# Rib-BabyBack.net
KiCad netlist of a schematic drawn in EAGLE
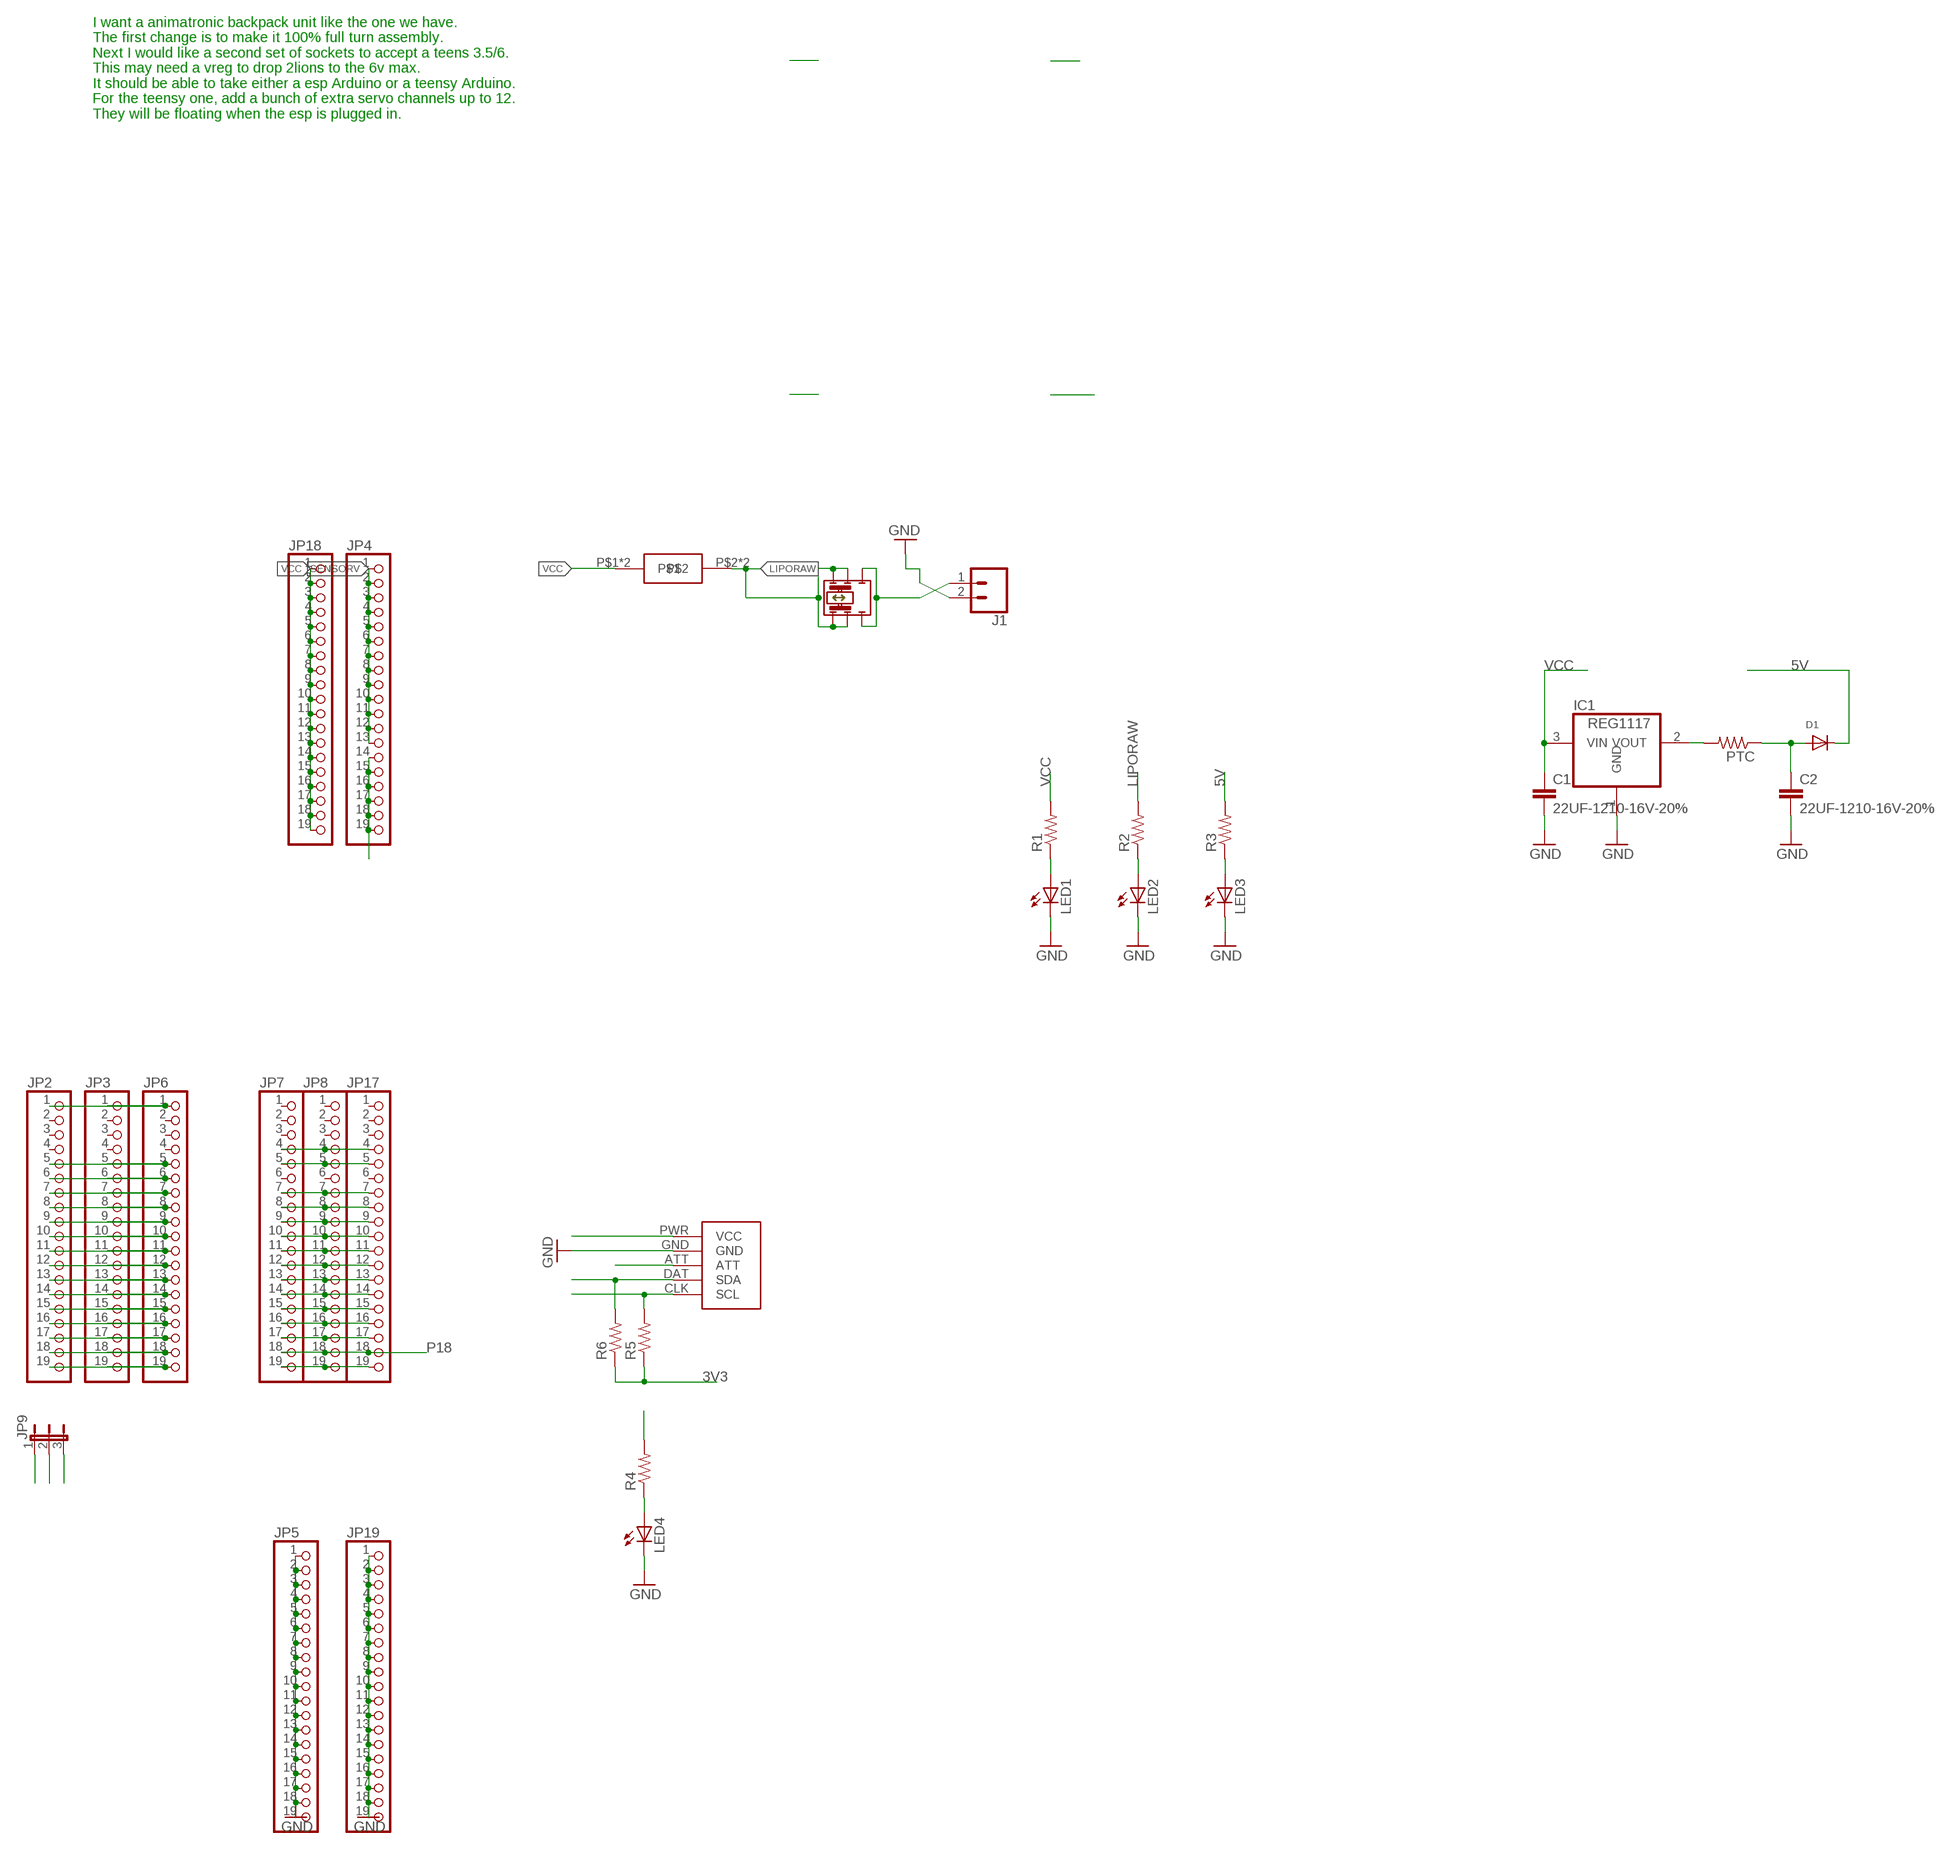
[diagram p0: schematic, sheet 1]

(export (version "E")
  (design (tool "Eeschema 10.0.6"))
  (components
    (comp (ref "C1")
      (value "22UF-1210-16V-20%")
      (footprint "eagle-import:1210")
      (libsource (lib "eagle-import") (part "22UF-1210-16V-20%"))
    )
    (comp (ref "C2")
      (value "22UF-1210-16V-20%")
      (footprint "eagle-import:1210")
      (libsource (lib "eagle-import") (part "22UF-1210-16V-20%"))
    )
    (comp (ref "D1")
      (value "DIODESOD-523")
      (footprint "eagle-import:SOD-523")
      (libsource (lib "eagle-import") (part "DIODESOD-523"))
    )
    (comp (ref "F4")
      (value "3557-2")
      (footprint "eagle-import:3557-2")
      (libsource (lib "eagle-import") (part "3557-2"))
    )
    (comp (ref "IC1")
      (value "REG1117")
      (footprint "eagle-import:SOT223")
      (libsource (lib "eagle-import") (part "REG1117"))
    )
    (comp (ref "J1")
      (value "CONN_023.5MM_LOCK")
      (footprint "eagle-import:SCREWTERMINAL-3.5MM-2_LOCK")
      (libsource (lib "eagle-import") (part "CONN_023.5MM_LOCK"))
    )
    (comp (ref "JP2")
      (value "PINHD-1X19")
      (footprint "eagle-import:1X19")
      (libsource (lib "eagle-import") (part "PINHD-1X19"))
    )
    (comp (ref "JP3")
      (value "PINHD-1X19")
      (footprint "eagle-import:1X19")
      (libsource (lib "eagle-import") (part "PINHD-1X19"))
    )
    (comp (ref "JP4")
      (value "PINHD-1X19")
      (footprint "eagle-import:1X19")
      (libsource (lib "eagle-import") (part "PINHD-1X19"))
    )
    (comp (ref "JP5")
      (value "PINHD-1X19")
      (footprint "eagle-import:1X19")
      (libsource (lib "eagle-import") (part "PINHD-1X19"))
    )
    (comp (ref "JP6")
      (value "PINHD-1X19")
      (footprint "eagle-import:1X19")
      (libsource (lib "eagle-import") (part "PINHD-1X19"))
    )
    (comp (ref "JP7")
      (value "PINHD-1X19")
      (footprint "eagle-import:1X19")
      (libsource (lib "eagle-import") (part "PINHD-1X19"))
    )
    (comp (ref "JP8")
      (value "PINHD-1X19")
      (footprint "eagle-import:1X19")
      (libsource (lib "eagle-import") (part "PINHD-1X19"))
    )
    (comp (ref "JP9")
      (value "JP2E")
      (footprint "eagle-import:JP2")
      (libsource (lib "eagle-import") (part "JP2E"))
    )
    (comp (ref "JP17")
      (value "PINHD-1X19")
      (footprint "eagle-import:1X19")
      (libsource (lib "eagle-import") (part "PINHD-1X19"))
    )
    (comp (ref "JP18")
      (value "PINHD-1X19")
      (footprint "eagle-import:1X19")
      (libsource (lib "eagle-import") (part "PINHD-1X19"))
    )
    (comp (ref "JP19")
      (value "PINHD-1X19")
      (footprint "eagle-import:1X19")
      (libsource (lib "eagle-import") (part "PINHD-1X19"))
    )
    (comp (ref "LED1")
      (value "LED_ESML0603")
      (footprint "eagle-import:LED_SML0603")
      (libsource (lib "eagle-import") (part "LED_ESML0603"))
    )
    (comp (ref "LED2")
      (value "LED_ESML0603")
      (footprint "eagle-import:LED_SML0603")
      (libsource (lib "eagle-import") (part "LED_ESML0603"))
    )
    (comp (ref "LED3")
      (value "LED_ESML0603")
      (footprint "eagle-import:LED_SML0603")
      (libsource (lib "eagle-import") (part "LED_ESML0603"))
    )
    (comp (ref "LED4")
      (value "LED_ESML0603")
      (footprint "eagle-import:LED_SML0603")
      (libsource (lib "eagle-import") (part "LED_ESML0603"))
    )
    (comp (ref "PTC")
      (value "R-US_R0805")
      (footprint "eagle-import:R0805")
      (libsource (lib "eagle-import") (part "R-US_R0805"))
    )
    (comp (ref "R1")
      (value "R-US_R0603")
      (footprint "eagle-import:R0603")
      (libsource (lib "eagle-import") (part "R-US_R0603"))
    )
    (comp (ref "R2")
      (value "R-US_R0603")
      (footprint "eagle-import:R0603")
      (libsource (lib "eagle-import") (part "R-US_R0603"))
    )
    (comp (ref "R3")
      (value "R-US_R0603")
      (footprint "eagle-import:R0603")
      (libsource (lib "eagle-import") (part "R-US_R0603"))
    )
    (comp (ref "R4")
      (value "R-US_R0603")
      (footprint "eagle-import:R0603")
      (libsource (lib "eagle-import") (part "R-US_R0603"))
    )
    (comp (ref "R5")
      (value "R-US_R0603")
      (footprint "eagle-import:R0603")
      (libsource (lib "eagle-import") (part "R-US_R0603"))
    )
    (comp (ref "R6")
      (value "R-US_R0603")
      (footprint "eagle-import:R0603")
      (libsource (lib "eagle-import") (part "R-US_R0603"))
    )
    (comp (ref "SW1")
      (value "DPDT")
      (footprint "eagle-import:GF-126-0327")
      (libsource (lib "eagle-import") (part "DPDT"))
    )
    (comp (ref "U$5")
      (value "WIICHUCK")
      (footprint "eagle-import:CHUCK")
      (libsource (lib "eagle-import") (part "WIICHUCK"))
    )
  )
  (nets
    (net (code "1") (name "/3V3") (class "Default")
      (node (ref "JP2") (pin "19") (pinfunction "19_19") (pintype "passive"))
      (node (ref "JP3") (pin "19") (pinfunction "19_19") (pintype "passive"))
      (node (ref "JP6") (pin "19") (pinfunction "19_19") (pintype "passive"))
      (node (ref "JP9") (pin "1") (pinfunction "1_1") (pintype "passive"))
      (node (ref "R5") (pin "1") (pinfunction "1_1") (pintype "passive"))
      (node (ref "R6") (pin "1") (pinfunction "1_1") (pintype "passive"))
      (node (ref "U$5") (pin "PWR") (pinfunction "VCC_PWR") (pintype "bidirectional"))
    )
    (net (code "2") (name "/5V") (class "Default")
      (node (ref "D1") (pin "K") (pinfunction "C_K") (pintype "passive"))
      (node (ref "JP2") (pin "1") (pinfunction "1_1") (pintype "passive"))
      (node (ref "JP3") (pin "1") (pinfunction "1_1") (pintype "passive"))
      (node (ref "JP4") (pin "14") (pinfunction "14_14") (pintype "passive"))
      (node (ref "JP4") (pin "15") (pinfunction "15_15") (pintype "passive"))
      (node (ref "JP4") (pin "16") (pinfunction "16_16") (pintype "passive"))
      (node (ref "JP4") (pin "17") (pinfunction "17_17") (pintype "passive"))
      (node (ref "JP4") (pin "18") (pinfunction "18_18") (pintype "passive"))
      (node (ref "JP4") (pin "19") (pinfunction "19_19") (pintype "passive"))
      (node (ref "JP6") (pin "1") (pinfunction "1_1") (pintype "passive"))
      (node (ref "JP9") (pin "3") (pinfunction "3_3") (pintype "passive"))
      (node (ref "R3") (pin "2") (pinfunction "2_2") (pintype "passive"))
    )
    (net (code "3") (name "/DET") (class "Default")
      (node (ref "JP2") (pin "9") (pinfunction "9_9") (pintype "passive"))
      (node (ref "JP3") (pin "9") (pinfunction "9_9") (pintype "passive"))
      (node (ref "JP6") (pin "9") (pinfunction "9_9") (pintype "passive"))
      (node (ref "U$5") (pin "ATT") (pinfunction "ATT_ATT") (pintype "bidirectional"))
    )
    (net (code "4") (name "/P13") (class "Default")
      (node (ref "JP2") (pin "5") (pinfunction "5_5") (pintype "passive"))
      (node (ref "JP3") (pin "5") (pinfunction "5_5") (pintype "passive"))
      (node (ref "JP6") (pin "5") (pinfunction "5_5") (pintype "passive"))
      (node (ref "R4") (pin "2") (pinfunction "2_2") (pintype "passive"))
    )
    (net (code "5") (name "/P18") (class "Default")
      (node (ref "JP17") (pin "18") (pinfunction "18_18") (pintype "passive"))
      (node (ref "JP7") (pin "18") (pinfunction "18_18") (pintype "passive"))
      (node (ref "JP8") (pin "18") (pinfunction "18_18") (pintype "passive"))
    )
    (net (code "6") (name "/SCL") (class "Default")
      (node (ref "JP17") (pin "17") (pinfunction "17_17") (pintype "passive"))
      (node (ref "JP7") (pin "17") (pinfunction "17_17") (pintype "passive"))
      (node (ref "JP8") (pin "17") (pinfunction "17_17") (pintype "passive"))
      (node (ref "R5") (pin "2") (pinfunction "2_2") (pintype "passive"))
      (node (ref "U$5") (pin "CLK") (pinfunction "SCL_CLK") (pintype "bidirectional"))
    )
    (net (code "7") (name "/SDA") (class "Default")
      (node (ref "JP17") (pin "14") (pinfunction "14_14") (pintype "passive"))
      (node (ref "JP7") (pin "14") (pinfunction "14_14") (pintype "passive"))
      (node (ref "JP8") (pin "14") (pinfunction "14_14") (pintype "passive"))
      (node (ref "R6") (pin "2") (pinfunction "2_2") (pintype "passive"))
      (node (ref "U$5") (pin "DAT") (pinfunction "SDA_DAT") (pintype "bidirectional"))
    )
    (net (code "8") (name "GND") (class "Default")
      (node (ref "C1") (pin "2") (pinfunction "2_2") (pintype "passive"))
      (node (ref "C2") (pin "2") (pinfunction "2_2") (pintype "passive"))
      (node (ref "IC1") (pin "1") (pinfunction "GND_1") (pintype "power_in"))
      (node (ref "J1") (pin "2") (pinfunction "2_2") (pintype "passive"))
      (node (ref "JP17") (pin "13") (pinfunction "13_13") (pintype "passive"))
      (node (ref "JP17") (pin "19") (pinfunction "19_19") (pintype "passive"))
      (node (ref "JP19") (pin "1") (pinfunction "1_1") (pintype "passive"))
      (node (ref "JP19") (pin "10") (pinfunction "10_10") (pintype "passive"))
      (node (ref "JP19") (pin "11") (pinfunction "11_11") (pintype "passive"))
      (node (ref "JP19") (pin "12") (pinfunction "12_12") (pintype "passive"))
      (node (ref "JP19") (pin "13") (pinfunction "13_13") (pintype "passive"))
      (node (ref "JP19") (pin "14") (pinfunction "14_14") (pintype "passive"))
      (node (ref "JP19") (pin "15") (pinfunction "15_15") (pintype "passive"))
      (node (ref "JP19") (pin "16") (pinfunction "16_16") (pintype "passive"))
      (node (ref "JP19") (pin "17") (pinfunction "17_17") (pintype "passive"))
      (node (ref "JP19") (pin "18") (pinfunction "18_18") (pintype "passive"))
      (node (ref "JP19") (pin "19") (pinfunction "19_19") (pintype "passive"))
      (node (ref "JP19") (pin "2") (pinfunction "2_2") (pintype "passive"))
      (node (ref "JP19") (pin "3") (pinfunction "3_3") (pintype "passive"))
      (node (ref "JP19") (pin "4") (pinfunction "4_4") (pintype "passive"))
      (node (ref "JP19") (pin "5") (pinfunction "5_5") (pintype "passive"))
      (node (ref "JP19") (pin "6") (pinfunction "6_6") (pintype "passive"))
      (node (ref "JP19") (pin "7") (pinfunction "7_7") (pintype "passive"))
      (node (ref "JP19") (pin "8") (pinfunction "8_8") (pintype "passive"))
      (node (ref "JP19") (pin "9") (pinfunction "9_9") (pintype "passive"))
      (node (ref "JP2") (pin "6") (pinfunction "6_6") (pintype "passive"))
      (node (ref "JP3") (pin "6") (pinfunction "6_6") (pintype "passive"))
      (node (ref "JP5") (pin "1") (pinfunction "1_1") (pintype "passive"))
      (node (ref "JP5") (pin "10") (pinfunction "10_10") (pintype "passive"))
      (node (ref "JP5") (pin "11") (pinfunction "11_11") (pintype "passive"))
      (node (ref "JP5") (pin "12") (pinfunction "12_12") (pintype "passive"))
      (node (ref "JP5") (pin "13") (pinfunction "13_13") (pintype "passive"))
      (node (ref "JP5") (pin "14") (pinfunction "14_14") (pintype "passive"))
      (node (ref "JP5") (pin "15") (pinfunction "15_15") (pintype "passive"))
      (node (ref "JP5") (pin "16") (pinfunction "16_16") (pintype "passive"))
      (node (ref "JP5") (pin "17") (pinfunction "17_17") (pintype "passive"))
      (node (ref "JP5") (pin "18") (pinfunction "18_18") (pintype "passive"))
      (node (ref "JP5") (pin "19") (pinfunction "19_19") (pintype "passive"))
      (node (ref "JP5") (pin "2") (pinfunction "2_2") (pintype "passive"))
      (node (ref "JP5") (pin "3") (pinfunction "3_3") (pintype "passive"))
      (node (ref "JP5") (pin "4") (pinfunction "4_4") (pintype "passive"))
      (node (ref "JP5") (pin "5") (pinfunction "5_5") (pintype "passive"))
      (node (ref "JP5") (pin "6") (pinfunction "6_6") (pintype "passive"))
      (node (ref "JP5") (pin "7") (pinfunction "7_7") (pintype "passive"))
      (node (ref "JP5") (pin "8") (pinfunction "8_8") (pintype "passive"))
      (node (ref "JP5") (pin "9") (pinfunction "9_9") (pintype "passive"))
      (node (ref "JP6") (pin "6") (pinfunction "6_6") (pintype "passive"))
      (node (ref "JP7") (pin "13") (pinfunction "13_13") (pintype "passive"))
      (node (ref "JP7") (pin "19") (pinfunction "19_19") (pintype "passive"))
      (node (ref "JP8") (pin "13") (pinfunction "13_13") (pintype "passive"))
      (node (ref "JP8") (pin "19") (pinfunction "19_19") (pintype "passive"))
      (node (ref "LED1") (pin "C") (pinfunction "C_C") (pintype "passive"))
      (node (ref "LED2") (pin "C") (pinfunction "C_C") (pintype "passive"))
      (node (ref "LED3") (pin "C") (pinfunction "C_C") (pintype "passive"))
      (node (ref "LED4") (pin "C") (pinfunction "C_C") (pintype "passive"))
      (node (ref "U$5") (pin "GND") (pinfunction "GND_GND") (pintype "bidirectional"))
    )
    (net (code "9") (name "LIPORAW") (class "Default")
      (node (ref "F4") (pin "P$2") (pinfunction "P$2_P$2") (pintype "bidirectional"))
      (node (ref "F4") (pin "P$3") (pinfunction "P$2_P$3") (pintype "bidirectional"))
      (node (ref "R2") (pin "2") (pinfunction "2_2") (pintype "passive"))
      (node (ref "SW1") (pin "A1") (pinfunction "A1_A1") (pintype "bidirectional"))
      (node (ref "SW1") (pin "A2") (pinfunction "A2_A2") (pintype "bidirectional"))
      (node (ref "SW1") (pin "B1") (pinfunction "B1_B1") (pintype "bidirectional"))
      (node (ref "SW1") (pin "B2") (pinfunction "B2_B2") (pintype "bidirectional"))
    )
    (net (code "10") (name "Net-(C2-Pad1)") (class "Default")
      (node (ref "C2") (pin "1") (pinfunction "1_1") (pintype "passive"))
      (node (ref "D1") (pin "A") (pinfunction "A_A") (pintype "passive"))
      (node (ref "PTC") (pin "1") (pinfunction "1_1") (pintype "passive"))
    )
    (net (code "11") (name "Net-(IC1-VOUT)") (class "Default")
      (node (ref "IC1") (pin "2") (pinfunction "VOUT_2") (pintype "output"))
      (node (ref "PTC") (pin "2") (pinfunction "2_2") (pintype "passive"))
    )
    (net (code "12") (name "Net-(J1-Pad1)") (class "Default")
      (node (ref "J1") (pin "1") (pinfunction "1_1") (pintype "passive"))
      (node (ref "SW1") (pin "C1") (pinfunction "C1_C1") (pintype "bidirectional"))
      (node (ref "SW1") (pin "C2") (pinfunction "C2_C2") (pintype "bidirectional"))
    )
    (net (code "13") (name "Net-(JP2-Pad7)") (class "Default")
      (node (ref "JP2") (pin "7") (pinfunction "7_7") (pintype "passive"))
      (node (ref "JP3") (pin "7") (pinfunction "7_7") (pintype "passive"))
      (node (ref "JP6") (pin "7") (pinfunction "7_7") (pintype "passive"))
    )
    (net (code "14") (name "Net-(JP2-Pad8)") (class "Default")
      (node (ref "JP2") (pin "8") (pinfunction "8_8") (pintype "passive"))
      (node (ref "JP3") (pin "8") (pinfunction "8_8") (pintype "passive"))
      (node (ref "JP6") (pin "8") (pinfunction "8_8") (pintype "passive"))
    )
    (net (code "15") (name "Net-(JP2-Pad10)") (class "Default")
      (node (ref "JP2") (pin "10") (pinfunction "10_10") (pintype "passive"))
      (node (ref "JP3") (pin "10") (pinfunction "10_10") (pintype "passive"))
      (node (ref "JP6") (pin "10") (pinfunction "10_10") (pintype "passive"))
    )
    (net (code "16") (name "Net-(JP2-Pad11)") (class "Default")
      (node (ref "JP2") (pin "11") (pinfunction "11_11") (pintype "passive"))
      (node (ref "JP3") (pin "11") (pinfunction "11_11") (pintype "passive"))
      (node (ref "JP6") (pin "11") (pinfunction "11_11") (pintype "passive"))
    )
    (net (code "17") (name "Net-(JP2-Pad12)") (class "Default")
      (node (ref "JP2") (pin "12") (pinfunction "12_12") (pintype "passive"))
      (node (ref "JP3") (pin "12") (pinfunction "12_12") (pintype "passive"))
      (node (ref "JP6") (pin "12") (pinfunction "12_12") (pintype "passive"))
    )
    (net (code "18") (name "Net-(JP2-Pad13)") (class "Default")
      (node (ref "JP2") (pin "13") (pinfunction "13_13") (pintype "passive"))
      (node (ref "JP3") (pin "13") (pinfunction "13_13") (pintype "passive"))
      (node (ref "JP6") (pin "13") (pinfunction "13_13") (pintype "passive"))
    )
    (net (code "19") (name "Net-(JP2-Pad14)") (class "Default")
      (node (ref "JP2") (pin "14") (pinfunction "14_14") (pintype "passive"))
      (node (ref "JP3") (pin "14") (pinfunction "14_14") (pintype "passive"))
      (node (ref "JP6") (pin "14") (pinfunction "14_14") (pintype "passive"))
    )
    (net (code "20") (name "Net-(JP2-Pad15)") (class "Default")
      (node (ref "JP2") (pin "15") (pinfunction "15_15") (pintype "passive"))
      (node (ref "JP3") (pin "15") (pinfunction "15_15") (pintype "passive"))
      (node (ref "JP6") (pin "15") (pinfunction "15_15") (pintype "passive"))
    )
    (net (code "21") (name "Net-(JP2-Pad16)") (class "Default")
      (node (ref "JP2") (pin "16") (pinfunction "16_16") (pintype "passive"))
      (node (ref "JP3") (pin "16") (pinfunction "16_16") (pintype "passive"))
      (node (ref "JP6") (pin "16") (pinfunction "16_16") (pintype "passive"))
    )
    (net (code "22") (name "Net-(JP2-Pad17)") (class "Default")
      (node (ref "JP2") (pin "17") (pinfunction "17_17") (pintype "passive"))
      (node (ref "JP3") (pin "17") (pinfunction "17_17") (pintype "passive"))
      (node (ref "JP6") (pin "17") (pinfunction "17_17") (pintype "passive"))
    )
    (net (code "23") (name "Net-(JP2-Pad18)") (class "Default")
      (node (ref "JP2") (pin "18") (pinfunction "18_18") (pintype "passive"))
      (node (ref "JP3") (pin "18") (pinfunction "18_18") (pintype "passive"))
      (node (ref "JP6") (pin "18") (pinfunction "18_18") (pintype "passive"))
    )
    (net (code "24") (name "Net-(JP17-Pad4)") (class "Default")
      (node (ref "JP17") (pin "4") (pinfunction "4_4") (pintype "passive"))
      (node (ref "JP7") (pin "4") (pinfunction "4_4") (pintype "passive"))
      (node (ref "JP8") (pin "4") (pinfunction "4_4") (pintype "passive"))
    )
    (net (code "25") (name "Net-(JP17-Pad5)") (class "Default")
      (node (ref "JP17") (pin "5") (pinfunction "5_5") (pintype "passive"))
      (node (ref "JP7") (pin "5") (pinfunction "5_5") (pintype "passive"))
      (node (ref "JP8") (pin "5") (pinfunction "5_5") (pintype "passive"))
    )
    (net (code "26") (name "Net-(JP17-Pad7)") (class "Default")
      (node (ref "JP17") (pin "7") (pinfunction "7_7") (pintype "passive"))
      (node (ref "JP7") (pin "7") (pinfunction "7_7") (pintype "passive"))
      (node (ref "JP8") (pin "7") (pinfunction "7_7") (pintype "passive"))
    )
    (net (code "27") (name "Net-(JP17-Pad8)") (class "Default")
      (node (ref "JP17") (pin "8") (pinfunction "8_8") (pintype "passive"))
      (node (ref "JP7") (pin "8") (pinfunction "8_8") (pintype "passive"))
      (node (ref "JP8") (pin "8") (pinfunction "8_8") (pintype "passive"))
    )
    (net (code "28") (name "Net-(JP17-Pad9)") (class "Default")
      (node (ref "JP17") (pin "9") (pinfunction "9_9") (pintype "passive"))
      (node (ref "JP7") (pin "9") (pinfunction "9_9") (pintype "passive"))
      (node (ref "JP8") (pin "9") (pinfunction "9_9") (pintype "passive"))
    )
    (net (code "29") (name "Net-(JP17-Pad10)") (class "Default")
      (node (ref "JP17") (pin "10") (pinfunction "10_10") (pintype "passive"))
      (node (ref "JP7") (pin "10") (pinfunction "10_10") (pintype "passive"))
      (node (ref "JP8") (pin "10") (pinfunction "10_10") (pintype "passive"))
    )
    (net (code "30") (name "Net-(JP17-Pad11)") (class "Default")
      (node (ref "JP17") (pin "11") (pinfunction "11_11") (pintype "passive"))
      (node (ref "JP7") (pin "11") (pinfunction "11_11") (pintype "passive"))
      (node (ref "JP8") (pin "11") (pinfunction "11_11") (pintype "passive"))
    )
    (net (code "31") (name "Net-(JP17-Pad12)") (class "Default")
      (node (ref "JP17") (pin "12") (pinfunction "12_12") (pintype "passive"))
      (node (ref "JP7") (pin "12") (pinfunction "12_12") (pintype "passive"))
      (node (ref "JP8") (pin "12") (pinfunction "12_12") (pintype "passive"))
    )
    (net (code "32") (name "Net-(JP17-Pad15)") (class "Default")
      (node (ref "JP17") (pin "15") (pinfunction "15_15") (pintype "passive"))
      (node (ref "JP7") (pin "15") (pinfunction "15_15") (pintype "passive"))
      (node (ref "JP8") (pin "15") (pinfunction "15_15") (pintype "passive"))
    )
    (net (code "33") (name "Net-(JP17-Pad16)") (class "Default")
      (node (ref "JP17") (pin "16") (pinfunction "16_16") (pintype "passive"))
      (node (ref "JP7") (pin "16") (pinfunction "16_16") (pintype "passive"))
      (node (ref "JP8") (pin "16") (pinfunction "16_16") (pintype "passive"))
    )
    (net (code "34") (name "Net-(LED1-PadA)") (class "Default")
      (node (ref "LED1") (pin "A") (pinfunction "A_A") (pintype "passive"))
      (node (ref "R1") (pin "1") (pinfunction "1_1") (pintype "passive"))
    )
    (net (code "35") (name "Net-(LED2-PadA)") (class "Default")
      (node (ref "LED2") (pin "A") (pinfunction "A_A") (pintype "passive"))
      (node (ref "R2") (pin "1") (pinfunction "1_1") (pintype "passive"))
    )
    (net (code "36") (name "Net-(LED3-PadA)") (class "Default")
      (node (ref "LED3") (pin "A") (pinfunction "A_A") (pintype "passive"))
      (node (ref "R3") (pin "1") (pinfunction "1_1") (pintype "passive"))
    )
    (net (code "37") (name "Net-(LED4-PadA)") (class "Default")
      (node (ref "LED4") (pin "A") (pinfunction "A_A") (pintype "passive"))
      (node (ref "R4") (pin "1") (pinfunction "1_1") (pintype "passive"))
    )
    (net (code "38") (name "SENSORV") (class "Default")
      (node (ref "JP4") (pin "1") (pinfunction "1_1") (pintype "passive"))
      (node (ref "JP4") (pin "10") (pinfunction "10_10") (pintype "passive"))
      (node (ref "JP4") (pin "11") (pinfunction "11_11") (pintype "passive"))
      (node (ref "JP4") (pin "12") (pinfunction "12_12") (pintype "passive"))
      (node (ref "JP4") (pin "13") (pinfunction "13_13") (pintype "passive"))
      (node (ref "JP4") (pin "2") (pinfunction "2_2") (pintype "passive"))
      (node (ref "JP4") (pin "3") (pinfunction "3_3") (pintype "passive"))
      (node (ref "JP4") (pin "4") (pinfunction "4_4") (pintype "passive"))
      (node (ref "JP4") (pin "5") (pinfunction "5_5") (pintype "passive"))
      (node (ref "JP4") (pin "6") (pinfunction "6_6") (pintype "passive"))
      (node (ref "JP4") (pin "7") (pinfunction "7_7") (pintype "passive"))
      (node (ref "JP4") (pin "8") (pinfunction "8_8") (pintype "passive"))
      (node (ref "JP4") (pin "9") (pinfunction "9_9") (pintype "passive"))
      (node (ref "JP9") (pin "2") (pinfunction "2_2") (pintype "passive"))
    )
    (net (code "39") (name "VCC") (class "Default")
      (node (ref "C1") (pin "1") (pinfunction "1_1") (pintype "passive"))
      (node (ref "F4") (pin "P$1") (pinfunction "P$1_P$1") (pintype "bidirectional"))
      (node (ref "F4") (pin "P$4") (pinfunction "P$1_P$4") (pintype "bidirectional"))
      (node (ref "IC1") (pin "3") (pinfunction "VIN_3") (pintype "input"))
      (node (ref "JP18") (pin "1") (pinfunction "1_1") (pintype "passive"))
      (node (ref "JP18") (pin "10") (pinfunction "10_10") (pintype "passive"))
      (node (ref "JP18") (pin "11") (pinfunction "11_11") (pintype "passive"))
      (node (ref "JP18") (pin "12") (pinfunction "12_12") (pintype "passive"))
      (node (ref "JP18") (pin "13") (pinfunction "13_13") (pintype "passive"))
      (node (ref "JP18") (pin "14") (pinfunction "14_14") (pintype "passive"))
      (node (ref "JP18") (pin "15") (pinfunction "15_15") (pintype "passive"))
      (node (ref "JP18") (pin "16") (pinfunction "16_16") (pintype "passive"))
      (node (ref "JP18") (pin "17") (pinfunction "17_17") (pintype "passive"))
      (node (ref "JP18") (pin "18") (pinfunction "18_18") (pintype "passive"))
      (node (ref "JP18") (pin "19") (pinfunction "19_19") (pintype "passive"))
      (node (ref "JP18") (pin "2") (pinfunction "2_2") (pintype "passive"))
      (node (ref "JP18") (pin "3") (pinfunction "3_3") (pintype "passive"))
      (node (ref "JP18") (pin "4") (pinfunction "4_4") (pintype "passive"))
      (node (ref "JP18") (pin "5") (pinfunction "5_5") (pintype "passive"))
      (node (ref "JP18") (pin "6") (pinfunction "6_6") (pintype "passive"))
      (node (ref "JP18") (pin "7") (pinfunction "7_7") (pintype "passive"))
      (node (ref "JP18") (pin "8") (pinfunction "8_8") (pintype "passive"))
      (node (ref "JP18") (pin "9") (pinfunction "9_9") (pintype "passive"))
      (node (ref "R1") (pin "2") (pinfunction "2_2") (pintype "passive"))
    )
    (net (code "40") (name "unconnected-(JP2-Pad2)") (class "Default")
      (node (ref "JP2") (pin "2") (pinfunction "2_2") (pintype "passive"))
    )
    (net (code "41") (name "unconnected-(JP2-Pad3)") (class "Default")
      (node (ref "JP2") (pin "3") (pinfunction "3_3") (pintype "passive"))
    )
    (net (code "42") (name "unconnected-(JP2-Pad4)") (class "Default")
      (node (ref "JP2") (pin "4") (pinfunction "4_4") (pintype "passive"))
    )
    (net (code "43") (name "unconnected-(JP3-Pad2)") (class "Default")
      (node (ref "JP3") (pin "2") (pinfunction "2_2") (pintype "passive"))
    )
    (net (code "44") (name "unconnected-(JP3-Pad3)") (class "Default")
      (node (ref "JP3") (pin "3") (pinfunction "3_3") (pintype "passive"))
    )
    (net (code "45") (name "unconnected-(JP3-Pad4)") (class "Default")
      (node (ref "JP3") (pin "4") (pinfunction "4_4") (pintype "passive"))
    )
    (net (code "46") (name "unconnected-(JP6-Pad2)") (class "Default")
      (node (ref "JP6") (pin "2") (pinfunction "2_2") (pintype "passive"))
    )
    (net (code "47") (name "unconnected-(JP6-Pad3)") (class "Default")
      (node (ref "JP6") (pin "3") (pinfunction "3_3") (pintype "passive"))
    )
    (net (code "48") (name "unconnected-(JP6-Pad4)") (class "Default")
      (node (ref "JP6") (pin "4") (pinfunction "4_4") (pintype "passive"))
    )
    (net (code "49") (name "unconnected-(JP7-Pad1)") (class "Default")
      (node (ref "JP7") (pin "1") (pinfunction "1_1") (pintype "passive"))
    )
    (net (code "50") (name "unconnected-(JP7-Pad2)") (class "Default")
      (node (ref "JP7") (pin "2") (pinfunction "2_2") (pintype "passive"))
    )
    (net (code "51") (name "unconnected-(JP7-Pad3)") (class "Default")
      (node (ref "JP7") (pin "3") (pinfunction "3_3") (pintype "passive"))
    )
    (net (code "52") (name "unconnected-(JP7-Pad6)") (class "Default")
      (node (ref "JP7") (pin "6") (pinfunction "6_6") (pintype "passive"))
    )
    (net (code "53") (name "unconnected-(JP8-Pad1)") (class "Default")
      (node (ref "JP8") (pin "1") (pinfunction "1_1") (pintype "passive"))
    )
    (net (code "54") (name "unconnected-(JP8-Pad2)") (class "Default")
      (node (ref "JP8") (pin "2") (pinfunction "2_2") (pintype "passive"))
    )
    (net (code "55") (name "unconnected-(JP8-Pad3)") (class "Default")
      (node (ref "JP8") (pin "3") (pinfunction "3_3") (pintype "passive"))
    )
    (net (code "56") (name "unconnected-(JP8-Pad6)") (class "Default")
      (node (ref "JP8") (pin "6") (pinfunction "6_6") (pintype "passive"))
    )
    (net (code "57") (name "unconnected-(JP17-Pad1)") (class "Default")
      (node (ref "JP17") (pin "1") (pinfunction "1_1") (pintype "passive"))
    )
    (net (code "58") (name "unconnected-(JP17-Pad2)") (class "Default")
      (node (ref "JP17") (pin "2") (pinfunction "2_2") (pintype "passive"))
    )
    (net (code "59") (name "unconnected-(JP17-Pad3)") (class "Default")
      (node (ref "JP17") (pin "3") (pinfunction "3_3") (pintype "passive"))
    )
    (net (code "60") (name "unconnected-(JP17-Pad6)") (class "Default")
      (node (ref "JP17") (pin "6") (pinfunction "6_6") (pintype "passive"))
    )
  )
)
